# HybrideNixieClock.net
KiCad netlist of a schematic drawn in EAGLE
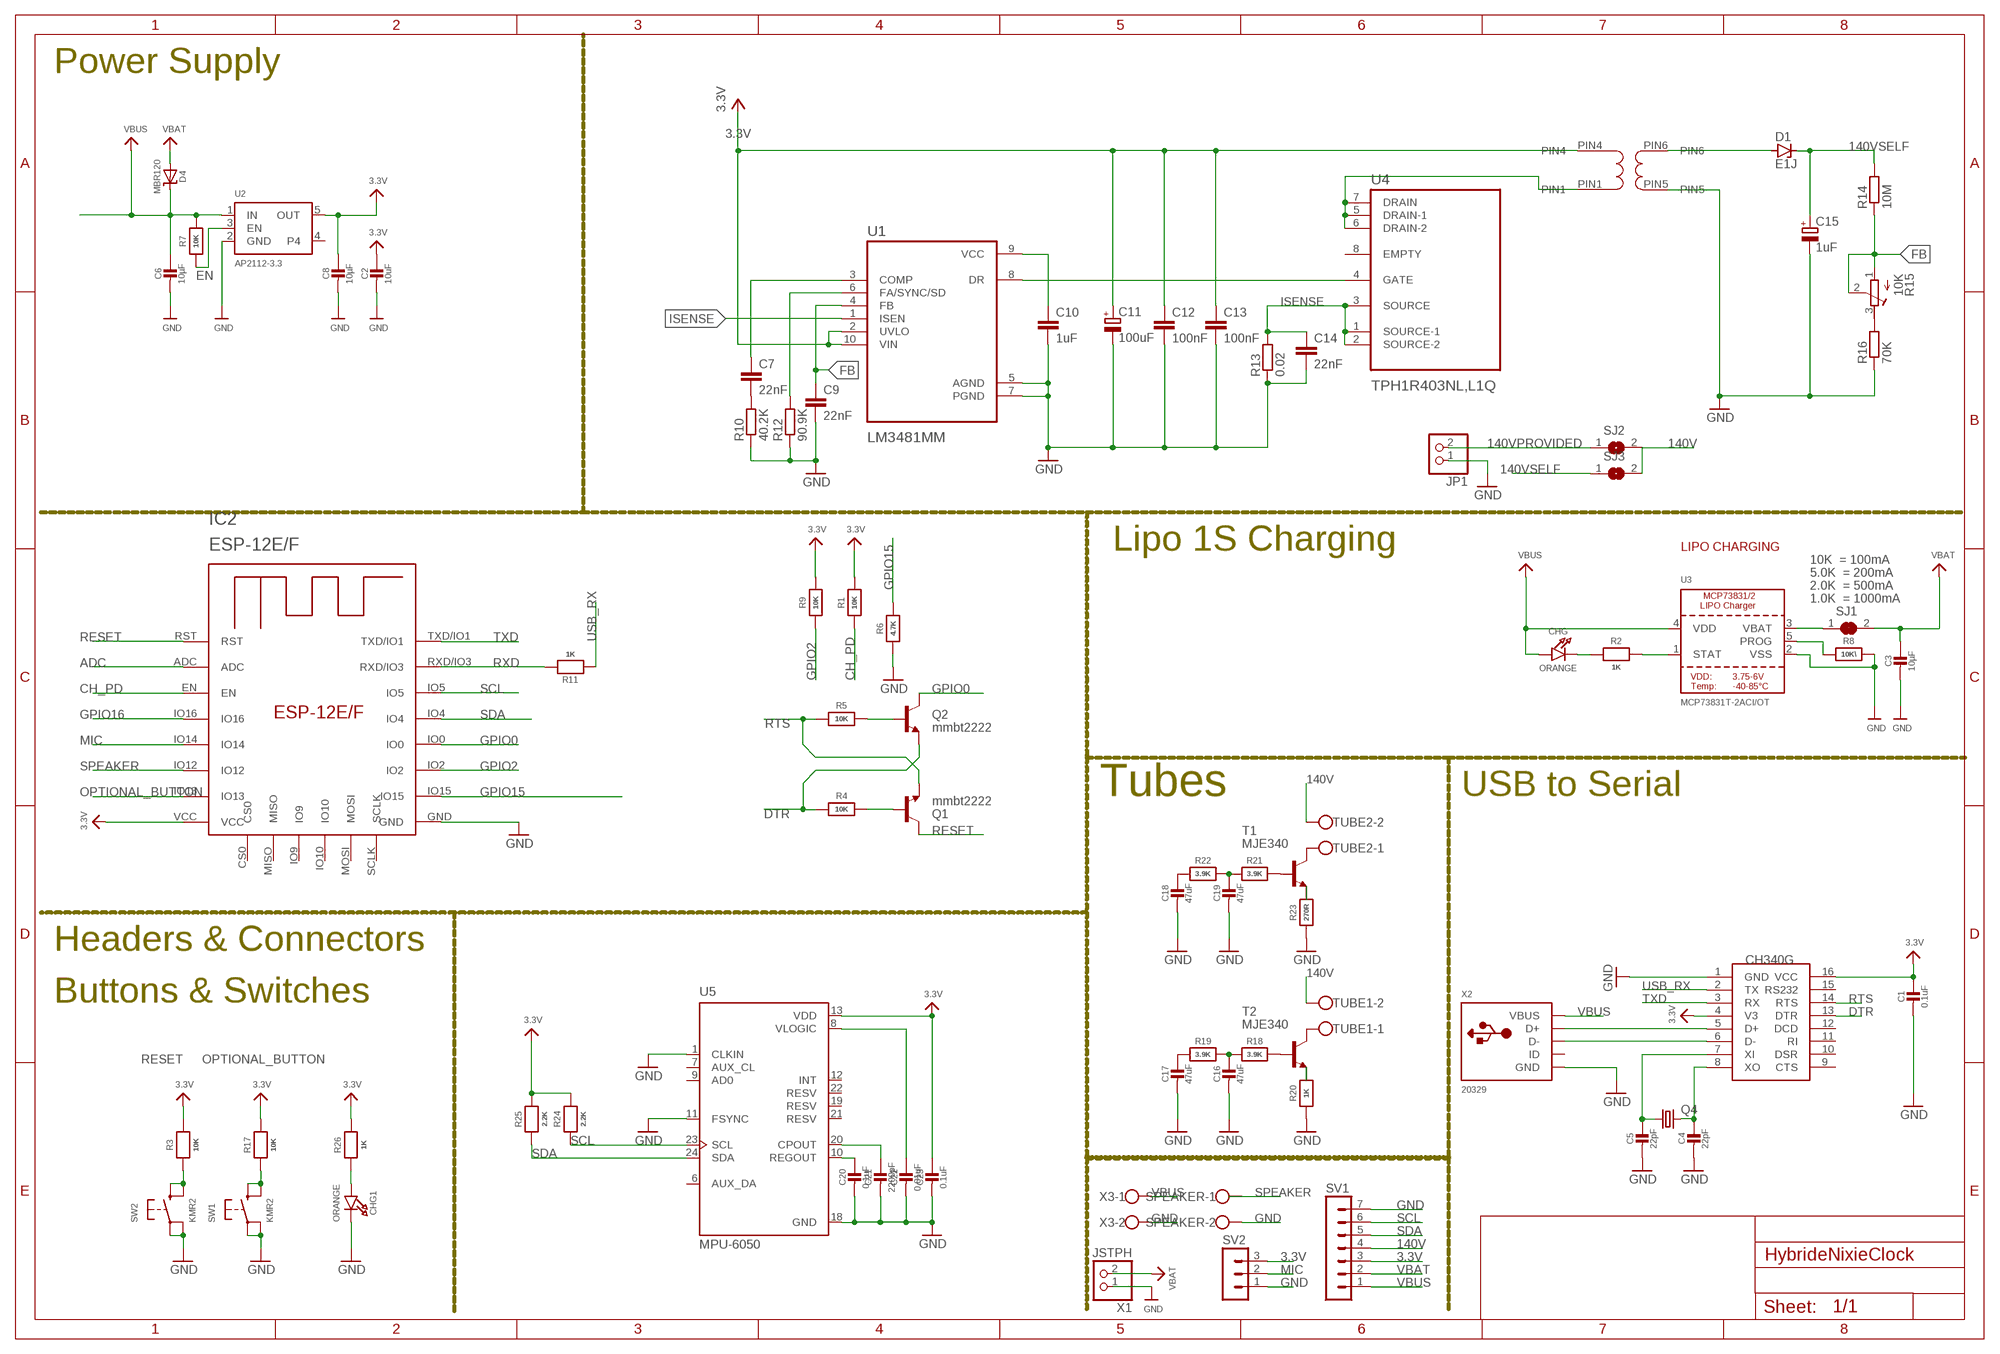
[diagram p0: schematic, sheet 1]

(export (version "E")
  (design (tool "Eeschema 10.0.6"))
  (components
    (comp (ref "C1")
      (value "0.1uF")
      (footprint "eagle-import:0603-NO")
      (libsource (lib "eagle-import") (part "CAP_CERAMIC0603_NO"))
    )
    (comp (ref "C2")
      (value "10uF")
      (footprint "eagle-import:0805-NO")
      (libsource (lib "eagle-import") (part "CAP_CERAMIC0805-NOOUTLINE"))
    )
    (comp (ref "C3")
      (value "10µF")
      (footprint "eagle-import:0805-NO")
      (libsource (lib "eagle-import") (part "CAP_CERAMIC0805-NOOUTLINE"))
    )
    (comp (ref "C4")
      (value "22pF")
      (footprint "eagle-import:0603-NO")
      (libsource (lib "eagle-import") (part "CAP_CERAMIC0603_NO"))
    )
    (comp (ref "C5")
      (value "22pF")
      (footprint "eagle-import:0603-NO")
      (libsource (lib "eagle-import") (part "CAP_CERAMIC0603_NO"))
    )
    (comp (ref "C6")
      (value "10µF")
      (footprint "eagle-import:0805-NO")
      (libsource (lib "eagle-import") (part "CAP_CERAMIC0805-NOOUTLINE"))
    )
    (comp (ref "C7")
      (value "22nF")
      (footprint "eagle-import:C0603")
      (libsource (lib "eagle-import") (part "C-EUC0603"))
    )
    (comp (ref "C8")
      (value "10µF")
      (footprint "eagle-import:0805-NO")
      (libsource (lib "eagle-import") (part "CAP_CERAMIC0805-NOOUTLINE"))
    )
    (comp (ref "C9")
      (value "22nF")
      (footprint "eagle-import:C0603")
      (libsource (lib "eagle-import") (part "C-EUC0603"))
    )
    (comp (ref "C10")
      (value "1uF")
      (footprint "eagle-import:C0603")
      (libsource (lib "eagle-import") (part "C-EUC0603"))
    )
    (comp (ref "C11")
      (value "100uF")
      (footprint "eagle-import:CT3216")
      (libsource (lib "eagle-import") (part "CPOL-EUCT3216"))
    )
    (comp (ref "C12")
      (value "100nF")
      (footprint "eagle-import:C0603")
      (libsource (lib "eagle-import") (part "C-EUC0603"))
    )
    (comp (ref "C13")
      (value "100nF")
      (footprint "eagle-import:C0603")
      (libsource (lib "eagle-import") (part "C-EUC0603"))
    )
    (comp (ref "C14")
      (value "22nF")
      (footprint "eagle-import:C0603")
      (libsource (lib "eagle-import") (part "C-EUC0603"))
    )
    (comp (ref "C15")
      (value "1uF")
      (footprint "eagle-import:CT3216")
      (libsource (lib "eagle-import") (part "CPOL-EUCT3216"))
    )
    (comp (ref "C16")
      (value "47uF")
      (footprint "eagle-import:0603-NO")
      (libsource (lib "eagle-import") (part "CAP_CERAMIC0603_NO"))
    )
    (comp (ref "C17")
      (value "47uF")
      (footprint "eagle-import:0603-NO")
      (libsource (lib "eagle-import") (part "CAP_CERAMIC0603_NO"))
    )
    (comp (ref "C18")
      (value "47uF")
      (footprint "eagle-import:0603-NO")
      (libsource (lib "eagle-import") (part "CAP_CERAMIC0603_NO"))
    )
    (comp (ref "C19")
      (value "47uF")
      (footprint "eagle-import:0603-NO")
      (libsource (lib "eagle-import") (part "CAP_CERAMIC0603_NO"))
    )
    (comp (ref "C20")
      (value "0.1uF")
      (footprint "eagle-import:0603-NO")
      (libsource (lib "eagle-import") (part "CAP_CERAMIC0603_NO"))
    )
    (comp (ref "C21")
      (value "2200pF")
      (footprint "eagle-import:0603-NO")
      (libsource (lib "eagle-import") (part "CAP_CERAMIC0603_NO"))
    )
    (comp (ref "C22")
      (value "0.01uF")
      (footprint "eagle-import:0603-NO")
      (libsource (lib "eagle-import") (part "CAP_CERAMIC0603_NO"))
    )
    (comp (ref "C23")
      (value "0.1uF")
      (footprint "eagle-import:0603-NO")
      (libsource (lib "eagle-import") (part "CAP_CERAMIC0603_NO"))
    )
    (comp (ref "CHG")
      (value "ORANGE")
      (footprint "eagle-import:CHIPLED_0805_NOOUTLINE")
      (libsource (lib "eagle-import") (part "LED0805_NOOUTLINE"))
    )
    (comp (ref "CHG1")
      (value "ORANGE")
      (footprint "eagle-import:CHIPLED_0805_NOOUTLINE")
      (libsource (lib "eagle-import") (part "LED0805_NOOUTLINE"))
    )
    (comp (ref "D1")
      (value "E1J")
      (footprint "eagle-import:SMB")
      (libsource (lib "eagle-import") (part "ZENER-DIODESMB"))
    )
    (comp (ref "D4")
      (value "MBR120")
      (footprint "eagle-import:SOD-123")
      (libsource (lib "eagle-import") (part "DIODE-SCHOTTKYSOD-123"))
    )
    (comp (ref "IC2")
      (value "ESP-12E/F")
      (footprint "eagle-import:ESP-12E")
      (libsource (lib "eagle-import") (part "ESP-12E/F"))
    )
    (comp (ref "JP1")
      (value "PINHD-1X2")
      (footprint "eagle-import:1X02")
      (libsource (lib "eagle-import") (part "PINHD-1X2"))
    )
    (comp (ref "Q1")
      (value "mmbt2222")
      (footprint "eagle-import:SOT23-3")
      (libsource (lib "eagle-import") (part "TRANSISTOR_NPNSOT23-3"))
    )
    (comp (ref "Q2")
      (value "mmbt2222")
      (footprint "eagle-import:SOT23-3")
      (libsource (lib "eagle-import") (part "TRANSISTOR_NPNSOT23-3"))
    )
    (comp (ref "Q4")
      (value "CRYSTALCTS406")
      (footprint "eagle-import:CTS406")
      (libsource (lib "eagle-import") (part "CRYSTALCTS406"))
    )
    (comp (ref "R1")
      (value "10K")
      (footprint "eagle-import:0603-NO")
      (libsource (lib "eagle-import") (part "RESISTOR_0603_NOOUT"))
    )
    (comp (ref "R2")
      (value "1K")
      (footprint "eagle-import:0603-NO")
      (libsource (lib "eagle-import") (part "RESISTOR_0603_NOOUT"))
    )
    (comp (ref "R3")
      (value "10K")
      (footprint "eagle-import:0603-NO")
      (libsource (lib "eagle-import") (part "RESISTOR_0603_NOOUT"))
    )
    (comp (ref "R4")
      (value "10K")
      (footprint "eagle-import:0603-NO")
      (libsource (lib "eagle-import") (part "RESISTOR_0603_NOOUT"))
    )
    (comp (ref "R5")
      (value "10K")
      (footprint "eagle-import:0603-NO")
      (libsource (lib "eagle-import") (part "RESISTOR_0603_NOOUT"))
    )
    (comp (ref "R6")
      (value "4.7K")
      (footprint "eagle-import:0603-NO")
      (libsource (lib "eagle-import") (part "RESISTOR_0603_NOOUT"))
    )
    (comp (ref "R7")
      (value "10K")
      (footprint "eagle-import:0603-NO")
      (libsource (lib "eagle-import") (part "RESISTOR_0603_NOOUT"))
    )
    (comp (ref "R8")
      (value "10K\\")
      (footprint "eagle-import:0603-NO")
      (libsource (lib "eagle-import") (part "RESISTOR_0603_NOOUT"))
    )
    (comp (ref "R9")
      (value "10K")
      (footprint "eagle-import:0603-NO")
      (libsource (lib "eagle-import") (part "RESISTOR_0603_NOOUT"))
    )
    (comp (ref "R10")
      (value "40.2K")
      (footprint "eagle-import:R0603")
      (libsource (lib "eagle-import") (part "R-EU_R0603"))
    )
    (comp (ref "R11")
      (value "1K")
      (footprint "eagle-import:_0603MP")
      (libsource (lib "eagle-import") (part "RESISTOR_0603MP"))
    )
    (comp (ref "R12")
      (value "90.9K")
      (footprint "eagle-import:R0603")
      (libsource (lib "eagle-import") (part "R-EU_R0603"))
    )
    (comp (ref "R13")
      (value "0.02")
      (footprint "eagle-import:R0603")
      (libsource (lib "eagle-import") (part "R-EU_R0603"))
    )
    (comp (ref "R14")
      (value "10M")
      (footprint "eagle-import:R0603")
      (libsource (lib "eagle-import") (part "R-EU_R0603"))
    )
    (comp (ref "R15")
      (value "10K")
      (footprint "eagle-import:RTRIM4G_J")
      (libsource (lib "eagle-import") (part "R-TRIMM4G/J"))
    )
    (comp (ref "R16")
      (value "70K")
      (footprint "eagle-import:R0603")
      (libsource (lib "eagle-import") (part "R-EU_R0603"))
    )
    (comp (ref "R17")
      (value "10K")
      (footprint "eagle-import:0603-NO")
      (libsource (lib "eagle-import") (part "RESISTOR_0603_NOOUT"))
    )
    (comp (ref "R18")
      (value "3.9K")
      (footprint "eagle-import:0603-NO")
      (libsource (lib "eagle-import") (part "RESISTOR_0603_NOOUT"))
    )
    (comp (ref "R19")
      (value "3.9K")
      (footprint "eagle-import:0603-NO")
      (libsource (lib "eagle-import") (part "RESISTOR_0603_NOOUT"))
    )
    (comp (ref "R20")
      (value "1K")
      (footprint "eagle-import:0603-NO")
      (libsource (lib "eagle-import") (part "RESISTOR_0603_NOOUT"))
    )
    (comp (ref "R21")
      (value "3.9K")
      (footprint "eagle-import:0603-NO")
      (libsource (lib "eagle-import") (part "RESISTOR_0603_NOOUT"))
    )
    (comp (ref "R22")
      (value "3.9K")
      (footprint "eagle-import:0603-NO")
      (libsource (lib "eagle-import") (part "RESISTOR_0603_NOOUT"))
    )
    (comp (ref "R23")
      (value "270R")
      (footprint "eagle-import:0603-NO")
      (libsource (lib "eagle-import") (part "RESISTOR_0603_NOOUT"))
    )
    (comp (ref "R24")
      (value "2.2K")
      (footprint "eagle-import:0603-NO")
      (libsource (lib "eagle-import") (part "RESISTOR_0603_NOOUT"))
    )
    (comp (ref "R25")
      (value "2.2K")
      (footprint "eagle-import:0603-NO")
      (libsource (lib "eagle-import") (part "RESISTOR_0603_NOOUT"))
    )
    (comp (ref "R26")
      (value "1K")
      (footprint "eagle-import:0603-NO")
      (libsource (lib "eagle-import") (part "RESISTOR_0603_NOOUT"))
    )
    (comp (ref "SJ1")
      (value "SOLDERJUMPER_CLOSED")
      (footprint "eagle-import:SOLDERJUMPER_CLOSEDWIRE")
      (libsource (lib "eagle-import") (part "SOLDERJUMPER_CLOSED"))
    )
    (comp (ref "SJ2") (value "SJ") (footprint "eagle-import:SJ") (libsource (lib "eagle-import") (part "SJ")))
    (comp (ref "SJ3") (value "SJ") (footprint "eagle-import:SJ") (libsource (lib "eagle-import") (part "SJ")))
    (comp (ref "SPEAKER")
      (value "W237-102")
      (footprint "eagle-import:W237-102")
      (fields (field (name "MPN") "237-102"))
      (libsource (lib "eagle-import") (part "W237-102"))
    )
    (comp (ref "SV1")
      (value "MA07-1")
      (footprint "eagle-import:MA07-1")
      (libsource (lib "eagle-import") (part "MA07-1"))
    )
    (comp (ref "SV2")
      (value "MA03-1")
      (footprint "eagle-import:MA03-1")
      (libsource (lib "eagle-import") (part "MA03-1"))
    )
    (comp (ref "SW1")
      (value "KMR2")
      (footprint "eagle-import:BTN_KMR2_4.6X2.8")
      (libsource (lib "eagle-import") (part "SWITCH_TACT_SMT4.6X2.8"))
    )
    (comp (ref "SW2")
      (value "KMR2")
      (footprint "eagle-import:BTN_KMR2_4.6X2.8")
      (libsource (lib "eagle-import") (part "SWITCH_TACT_SMT4.6X2.8"))
    )
    (comp (ref "T1")
      (value "MJE340")
      (footprint "eagle-import:TO126")
      (fields (field (name "MF") "STMicroelectronics"))
      (libsource (lib "eagle-import") (part "MJE340"))
    )
    (comp (ref "T2")
      (value "MJE340")
      (footprint "eagle-import:TO126")
      (fields (field (name "MF") "STMicroelectronics"))
      (libsource (lib "eagle-import") (part "MJE340"))
    )
    (comp (ref "TUBE1")
      (value "W237-102")
      (footprint "eagle-import:W237-102")
      (fields (field (name "MPN") "237-102"))
      (libsource (lib "eagle-import") (part "W237-102"))
    )
    (comp (ref "TUBE2")
      (value "W237-102")
      (footprint "eagle-import:W237-102")
      (fields (field (name "MPN") "237-102"))
      (libsource (lib "eagle-import") (part "W237-102"))
    )
    (comp (ref "U$6")
      (value "TTRN-060S-013")
      (footprint "eagle-import:TTRN-060S-013")
      (libsource (lib "eagle-import") (part "TTRN-060S-013"))
    )
    (comp (ref "U$7")
      (value "CH340G")
      (footprint "eagle-import:SOIC16")
      (libsource (lib "eagle-import") (part "CH340G"))
    )
    (comp (ref "U1")
      (value "LM3481MM")
      (footprint "eagle-import:SOP50P490X110-10N")
      (fields (field (name "MF") "Texas Instruments") (field (name "MP") "LM3481MM/NOPB"))
      (libsource (lib "eagle-import") (part "LM3481MM"))
    )
    (comp (ref "U2")
      (value "AP2112-3.3")
      (footprint "eagle-import:SOT23-5")
      (libsource (lib "eagle-import") (part "VREG_SOT23-5"))
    )
    (comp (ref "U3")
      (value "MCP73831T-2ACI/OT")
      (footprint "eagle-import:SOT23-5")
      (libsource (lib "eagle-import") (part "MCP73831/2"))
    )
    (comp (ref "U4")
      (value "TPH1R403NL,L1Q")
      (footprint "eagle-import:TRANS_TPHR8504PL,L1Q")
      (fields (field (name "MF") "Toshiba Semiconductor"))
      (libsource (lib "eagle-import") (part "TPH1R403NL,L1Q"))
    )
    (comp (ref "U5")
      (value "MPU-6050")
      (footprint "eagle-import:QFN50P400X400X95-24N")
      (fields (field (name "MF") "TDK InvenSense"))
      (libsource (lib "eagle-import") (part "MPU-6050"))
    )
    (comp (ref "X1")
      (value "JSTPH")
      (footprint "eagle-import:JSTPH2")
      (libsource (lib "eagle-import") (part "CON_JST_PH_2PIN"))
    )
    (comp (ref "X2")
      (value "20329")
      (footprint "eagle-import:4UCONN_20329_V2")
      (libsource (lib "eagle-import") (part "USB_MICRO_20329_V2"))
    )
    (comp (ref "X3")
      (value "W237-102")
      (footprint "eagle-import:W237-102")
      (fields (field (name "MPN") "237-102"))
      (libsource (lib "eagle-import") (part "W237-102"))
    )
  )
  (nets
    (net (code "1") (name "/140V") (class "Default")
      (node (ref "SJ2") (pin "2") (pinfunction "2_2") (pintype "passive"))
      (node (ref "SJ3") (pin "2") (pinfunction "2_2") (pintype "passive"))
      (node (ref "SV1") (pin "4") (pinfunction "4_4") (pintype "passive"))
      (node (ref "TUBE1") (pin "2") (pinfunction "KL_2") (pintype "passive"))
      (node (ref "TUBE2") (pin "2") (pinfunction "KL_2") (pintype "passive"))
    )
    (net (code "2") (name "/140VPROVIDED") (class "Default")
      (node (ref "JP1") (pin "2") (pinfunction "2_2") (pintype "passive"))
      (node (ref "SJ2") (pin "1") (pinfunction "1_1") (pintype "passive"))
    )
    (net (code "3") (name "/140VSELF") (class "Default")
      (node (ref "C15") (pin "+") (pinfunction "+_+") (pintype "passive"))
      (node (ref "D1") (pin "C") (pinfunction "C_C") (pintype "passive"))
      (node (ref "R14") (pin "2") (pinfunction "2_2") (pintype "passive"))
      (node (ref "SJ3") (pin "1") (pinfunction "1_1") (pintype "passive"))
    )
    (net (code "4") (name "/ADC") (class "Default")
      (node (ref "IC2") (pin "ADC") (pinfunction "ADC_ADC") (pintype "bidirectional"))
    )
    (net (code "5") (name "/CH_PD") (class "Default")
      (node (ref "IC2") (pin "EN") (pinfunction "EN_EN") (pintype "bidirectional"))
      (node (ref "R1") (pin "1") (pinfunction "1_1") (pintype "passive"))
    )
    (net (code "6") (name "/DTR") (class "Default")
      (node (ref "Q2") (pin "2") (pinfunction "E_2") (pintype "passive"))
      (node (ref "R4") (pin "1") (pinfunction "1_1") (pintype "passive"))
      (node (ref "U$7") (pin "13") (pinfunction "DTR_13") (pintype "bidirectional"))
    )
    (net (code "7") (name "/EN") (class "Default")
      (node (ref "R7") (pin "1") (pinfunction "1_1") (pintype "passive"))
      (node (ref "U2") (pin "3") (pinfunction "EN_3") (pintype "input"))
    )
    (net (code "8") (name "/GPIO0") (class "Default")
      (node (ref "IC2") (pin "IO0") (pinfunction "IO0_IO0") (pintype "bidirectional"))
      (node (ref "Q2") (pin "3") (pinfunction "C_3") (pintype "passive"))
    )
    (net (code "9") (name "/GPIO2") (class "Default")
      (node (ref "IC2") (pin "IO2") (pinfunction "IO2_IO2") (pintype "bidirectional"))
      (node (ref "R9") (pin "1") (pinfunction "1_1") (pintype "passive"))
    )
    (net (code "10") (name "/GPIO15") (class "Default")
      (node (ref "IC2") (pin "IO15") (pinfunction "IO15_IO15") (pintype "bidirectional"))
      (node (ref "R6") (pin "2") (pinfunction "2_2") (pintype "passive"))
    )
    (net (code "11") (name "/GPIO16") (class "Default")
      (node (ref "IC2") (pin "IO16") (pinfunction "IO16_IO16") (pintype "bidirectional"))
    )
    (net (code "12") (name "/MIC") (class "Default")
      (node (ref "IC2") (pin "IO14") (pinfunction "IO14_IO14") (pintype "bidirectional"))
      (node (ref "SV2") (pin "2") (pinfunction "2_2") (pintype "passive"))
    )
    (net (code "13") (name "/N$11") (class "Default")
      (node (ref "D1") (pin "A") (pinfunction "A_A") (pintype "passive"))
      (node (ref "U$6") (pin "PIN6") (pinfunction "PIN6_PIN6") (pintype "bidirectional"))
      (node (ref "U1") (pin "8") (pinfunction "DR_8") (pintype "output"))
      (node (ref "U4") (pin "4") (pinfunction "GATE_4") (pintype "bidirectional"))
    )
    (net (code "14") (name "/OPTIONAL_BUTTON") (class "Default")
      (node (ref "IC2") (pin "IO13") (pinfunction "IO13_IO13") (pintype "bidirectional"))
      (node (ref "R17") (pin "1") (pinfunction "1_1") (pintype "passive"))
      (node (ref "SW1") (pin "B") (pinfunction "S_B") (pintype "passive"))
      (node (ref "SW1") (pin "B'") (pinfunction "S1_B'") (pintype "passive"))
    )
    (net (code "15") (name "/RESET") (class "Default")
      (node (ref "IC2") (pin "RST") (pinfunction "RST_RST") (pintype "input"))
      (node (ref "Q1") (pin "3") (pinfunction "C_3") (pintype "passive"))
      (node (ref "R3") (pin "1") (pinfunction "1_1") (pintype "passive"))
      (node (ref "SW2") (pin "B") (pinfunction "S_B") (pintype "passive"))
      (node (ref "SW2") (pin "B'") (pinfunction "S1_B'") (pintype "passive"))
    )
    (net (code "16") (name "/RTS") (class "Default")
      (node (ref "Q1") (pin "2") (pinfunction "E_2") (pintype "passive"))
      (node (ref "R5") (pin "1") (pinfunction "1_1") (pintype "passive"))
      (node (ref "U$7") (pin "14") (pinfunction "RTS_14") (pintype "bidirectional"))
    )
    (net (code "17") (name "/RXD") (class "Default")
      (node (ref "IC2") (pin "RXD/IO3") (pinfunction "RXD/IO3_RXD/IO3") (pintype "bidirectional"))
      (node (ref "R11") (pin "2") (pinfunction "2_2") (pintype "passive"))
    )
    (net (code "18") (name "/SCL") (class "Default")
      (node (ref "IC2") (pin "IO5") (pinfunction "IO5_IO5") (pintype "bidirectional"))
      (node (ref "R24") (pin "1") (pinfunction "1_1") (pintype "passive"))
      (node (ref "SV1") (pin "6") (pinfunction "6_6") (pintype "passive"))
      (node (ref "U5") (pin "23") (pinfunction "SCL_23") (pintype "input"))
    )
    (net (code "19") (name "/SDA") (class "Default")
      (node (ref "IC2") (pin "IO4") (pinfunction "IO4_IO4") (pintype "bidirectional"))
      (node (ref "R25") (pin "1") (pinfunction "1_1") (pintype "passive"))
      (node (ref "SV1") (pin "5") (pinfunction "5_5") (pintype "passive"))
      (node (ref "U5") (pin "24") (pinfunction "SDA_24") (pintype "bidirectional"))
    )
    (net (code "20") (name "/SPEAKER") (class "Default")
      (node (ref "IC2") (pin "IO12") (pinfunction "IO12_IO12") (pintype "bidirectional"))
      (node (ref "SPEAKER") (pin "1") (pinfunction "KL_1") (pintype "passive"))
    )
    (net (code "21") (name "/TXD") (class "Default")
      (node (ref "IC2") (pin "TXD/IO1") (pinfunction "TXD/IO1_TXD/IO1") (pintype "bidirectional"))
      (node (ref "U$7") (pin "3") (pinfunction "RX_3") (pintype "bidirectional"))
    )
    (net (code "22") (name "/USB_RX") (class "Default")
      (node (ref "R11") (pin "1") (pinfunction "1_1") (pintype "passive"))
      (node (ref "U$7") (pin "2") (pinfunction "TX_2") (pintype "bidirectional"))
    )
    (net (code "23") (name "3.3V") (class "Default")
      (node (ref "C1") (pin "1") (pinfunction "1_1") (pintype "passive"))
      (node (ref "C11") (pin "+") (pinfunction "+_+") (pintype "passive"))
      (node (ref "C12") (pin "1") (pinfunction "1_1") (pintype "passive"))
      (node (ref "C13") (pin "1") (pinfunction "1_1") (pintype "passive"))
      (node (ref "C2") (pin "1") (pinfunction "1_1") (pintype "passive"))
      (node (ref "C23") (pin "1") (pinfunction "1_1") (pintype "passive"))
      (node (ref "C8") (pin "1") (pinfunction "1_1") (pintype "passive"))
      (node (ref "IC2") (pin "VCC") (pinfunction "VCC_VCC") (pintype "power_in"))
      (node (ref "R1") (pin "2") (pinfunction "2_2") (pintype "passive"))
      (node (ref "R17") (pin "2") (pinfunction "2_2") (pintype "passive"))
      (node (ref "R24") (pin "2") (pinfunction "2_2") (pintype "passive"))
      (node (ref "R25") (pin "2") (pinfunction "2_2") (pintype "passive"))
      (node (ref "R26") (pin "2") (pinfunction "2_2") (pintype "passive"))
      (node (ref "R3") (pin "2") (pinfunction "2_2") (pintype "passive"))
      (node (ref "R9") (pin "2") (pinfunction "2_2") (pintype "passive"))
      (node (ref "SV1") (pin "3") (pinfunction "3_3") (pintype "passive"))
      (node (ref "SV2") (pin "3") (pinfunction "3_3") (pintype "passive"))
      (node (ref "U$6") (pin "PIN4") (pinfunction "PIN4_PIN4") (pintype "bidirectional"))
      (node (ref "U$7") (pin "16") (pinfunction "VCC_16") (pintype "bidirectional"))
      (node (ref "U$7") (pin "4") (pinfunction "V3_4") (pintype "bidirectional"))
      (node (ref "U1") (pin "10") (pinfunction "VIN_10") (pintype "input"))
      (node (ref "U1") (pin "2") (pinfunction "UVLO_2") (pintype "input"))
      (node (ref "U2") (pin "5") (pinfunction "OUT_5") (pintype "power_in"))
      (node (ref "U5") (pin "13") (pinfunction "VDD_13") (pintype "power_in"))
    )
    (net (code "24") (name "FB") (class "Default")
      (node (ref "C9") (pin "1") (pinfunction "1_1") (pintype "passive"))
      (node (ref "R14") (pin "1") (pinfunction "1_1") (pintype "passive"))
      (node (ref "R15") (pin "1") (pinfunction "A_1") (pintype "passive"))
      (node (ref "R15") (pin "2") (pinfunction "S_2") (pintype "passive"))
      (node (ref "U1") (pin "4") (pinfunction "FB_4") (pintype "input"))
    )
    (net (code "25") (name "GND") (class "Default")
      (node (ref "C1") (pin "2") (pinfunction "2_2") (pintype "passive"))
      (node (ref "C10") (pin "2") (pinfunction "2_2") (pintype "passive"))
      (node (ref "C11") (pin "-") (pinfunction "-_-") (pintype "passive"))
      (node (ref "C12") (pin "2") (pinfunction "2_2") (pintype "passive"))
      (node (ref "C13") (pin "2") (pinfunction "2_2") (pintype "passive"))
      (node (ref "C14") (pin "2") (pinfunction "2_2") (pintype "passive"))
      (node (ref "C15") (pin "-") (pinfunction "-_-") (pintype "passive"))
      (node (ref "C16") (pin "2") (pinfunction "2_2") (pintype "passive"))
      (node (ref "C17") (pin "2") (pinfunction "2_2") (pintype "passive"))
      (node (ref "C18") (pin "2") (pinfunction "2_2") (pintype "passive"))
      (node (ref "C19") (pin "2") (pinfunction "2_2") (pintype "passive"))
      (node (ref "C2") (pin "2") (pinfunction "2_2") (pintype "passive"))
      (node (ref "C20") (pin "2") (pinfunction "2_2") (pintype "passive"))
      (node (ref "C21") (pin "2") (pinfunction "2_2") (pintype "passive"))
      (node (ref "C22") (pin "2") (pinfunction "2_2") (pintype "passive"))
      (node (ref "C23") (pin "2") (pinfunction "2_2") (pintype "passive"))
      (node (ref "C3") (pin "2") (pinfunction "2_2") (pintype "passive"))
      (node (ref "C4") (pin "2") (pinfunction "2_2") (pintype "passive"))
      (node (ref "C5") (pin "2") (pinfunction "2_2") (pintype "passive"))
      (node (ref "C6") (pin "2") (pinfunction "2_2") (pintype "passive"))
      (node (ref "C8") (pin "2") (pinfunction "2_2") (pintype "passive"))
      (node (ref "C9") (pin "2") (pinfunction "2_2") (pintype "passive"))
      (node (ref "CHG1") (pin "C") (pinfunction "C_C") (pintype "passive"))
      (node (ref "IC2") (pin "GND") (pinfunction "GND_GND") (pintype "power_in"))
      (node (ref "JP1") (pin "1") (pinfunction "1_1") (pintype "passive"))
      (node (ref "R10") (pin "1") (pinfunction "1_1") (pintype "passive"))
      (node (ref "R12") (pin "1") (pinfunction "1_1") (pintype "passive"))
      (node (ref "R13") (pin "1") (pinfunction "1_1") (pintype "passive"))
      (node (ref "R16") (pin "1") (pinfunction "1_1") (pintype "passive"))
      (node (ref "R20") (pin "1") (pinfunction "1_1") (pintype "passive"))
      (node (ref "R23") (pin "1") (pinfunction "1_1") (pintype "passive"))
      (node (ref "R6") (pin "1") (pinfunction "1_1") (pintype "passive"))
      (node (ref "R8") (pin "2") (pinfunction "2_2") (pintype "passive"))
      (node (ref "SPEAKER") (pin "2") (pinfunction "KL_2") (pintype "passive"))
      (node (ref "SV1") (pin "7") (pinfunction "7_7") (pintype "passive"))
      (node (ref "SV2") (pin "1") (pinfunction "1_1") (pintype "passive"))
      (node (ref "SW1") (pin "A") (pinfunction "P_A") (pintype "passive"))
      (node (ref "SW1") (pin "A'") (pinfunction "P1_A'") (pintype "passive"))
      (node (ref "SW2") (pin "A") (pinfunction "P_A") (pintype "passive"))
      (node (ref "SW2") (pin "A'") (pinfunction "P1_A'") (pintype "passive"))
      (node (ref "U$6") (pin "PIN5") (pinfunction "PIN5_PIN5") (pintype "bidirectional"))
      (node (ref "U$7") (pin "1") (pinfunction "GND_1") (pintype "bidirectional"))
      (node (ref "U1") (pin "5") (pinfunction "AGND_5") (pintype "power_in"))
      (node (ref "U1") (pin "7") (pinfunction "PGND_7") (pintype "power_in"))
      (node (ref "U2") (pin "2") (pinfunction "GND_2") (pintype "power_in"))
      (node (ref "U3") (pin "2") (pinfunction "VSS_2") (pintype "power_in"))
      (node (ref "U5") (pin "1") (pinfunction "CLKIN_1") (pintype "input"))
      (node (ref "U5") (pin "11") (pinfunction "FSYNC_11") (pintype "input"))
      (node (ref "U5") (pin "18") (pinfunction "GND_18") (pintype "power_in"))
      (node (ref "X1") (pin "1") (pinfunction "1_1") (pintype "passive"))
      (node (ref "X2") (pin "BASE@1") (pinfunction "GND_BASE@1") (pintype "power_in"))
      (node (ref "X2") (pin "BASE@2") (pinfunction "GND_BASE@2") (pintype "power_in"))
      (node (ref "X2") (pin "GND") (pinfunction "GND_GND") (pintype "power_in"))
      (node (ref "X2") (pin "SPRT@1") (pinfunction "GND_SPRT@1") (pintype "power_in"))
      (node (ref "X2") (pin "SPRT@2") (pinfunction "GND_SPRT@2") (pintype "power_in"))
      (node (ref "X2") (pin "SPRT@3") (pinfunction "GND_SPRT@3") (pintype "power_in"))
      (node (ref "X2") (pin "SPRT@4") (pinfunction "GND_SPRT@4") (pintype "power_in"))
      (node (ref "X3") (pin "2") (pinfunction "KL_2") (pintype "passive"))
    )
    (net (code "26") (name "ISENSE") (class "Default")
      (node (ref "C14") (pin "1") (pinfunction "1_1") (pintype "passive"))
      (node (ref "R13") (pin "2") (pinfunction "2_2") (pintype "passive"))
      (node (ref "U1") (pin "1") (pinfunction "ISEN_1") (pintype "input"))
      (node (ref "U4") (pin "1") (pinfunction "SOURCE-1_1") (pintype "bidirectional"))
      (node (ref "U4") (pin "2") (pinfunction "SOURCE-2_2") (pintype "bidirectional"))
      (node (ref "U4") (pin "3") (pinfunction "SOURCE_3") (pintype "bidirectional"))
    )
    (net (code "27") (name "Net-(C7-Pad2)") (class "Default")
      (node (ref "C7") (pin "2") (pinfunction "2_2") (pintype "passive"))
      (node (ref "R10") (pin "2") (pinfunction "2_2") (pintype "passive"))
    )
    (net (code "28") (name "Net-(C16-Pad1)") (class "Default")
      (node (ref "C16") (pin "1") (pinfunction "1_1") (pintype "passive"))
      (node (ref "R18") (pin "1") (pinfunction "1_1") (pintype "passive"))
      (node (ref "R19") (pin "2") (pinfunction "2_2") (pintype "passive"))
    )
    (net (code "29") (name "Net-(C17-Pad1)") (class "Default")
      (node (ref "C17") (pin "1") (pinfunction "1_1") (pintype "passive"))
      (node (ref "R19") (pin "1") (pinfunction "1_1") (pintype "passive"))
    )
    (net (code "30") (name "Net-(C18-Pad1)") (class "Default")
      (node (ref "C18") (pin "1") (pinfunction "1_1") (pintype "passive"))
      (node (ref "R22") (pin "1") (pinfunction "1_1") (pintype "passive"))
    )
    (net (code "31") (name "Net-(C19-Pad1)") (class "Default")
      (node (ref "C19") (pin "1") (pinfunction "1_1") (pintype "passive"))
      (node (ref "R21") (pin "1") (pinfunction "1_1") (pintype "passive"))
      (node (ref "R22") (pin "2") (pinfunction "2_2") (pintype "passive"))
    )
    (net (code "32") (name "Net-(CHG-PadC)") (class "Default")
      (node (ref "CHG") (pin "C") (pinfunction "C_C") (pintype "passive"))
      (node (ref "R2") (pin "1") (pinfunction "1_1") (pintype "passive"))
    )
    (net (code "33") (name "Net-(CHG1-PadA)") (class "Default")
      (node (ref "CHG1") (pin "A") (pinfunction "A_A") (pintype "passive"))
      (node (ref "R26") (pin "1") (pinfunction "1_1") (pintype "passive"))
    )
    (net (code "34") (name "Net-(Q1-B)") (class "Default")
      (node (ref "Q1") (pin "1") (pinfunction "B_1") (pintype "passive"))
      (node (ref "R4") (pin "2") (pinfunction "2_2") (pintype "passive"))
    )
    (net (code "35") (name "Net-(Q2-B)") (class "Default")
      (node (ref "Q2") (pin "1") (pinfunction "B_1") (pintype "passive"))
      (node (ref "R5") (pin "2") (pinfunction "2_2") (pintype "passive"))
    )
    (net (code "36") (name "Net-(Q4-2)") (class "Default")
      (node (ref "C4") (pin "1") (pinfunction "1_1") (pintype "passive"))
      (node (ref "Q4") (pin "3") (pinfunction "2_3") (pintype "passive"))
      (node (ref "U$7") (pin "8") (pinfunction "XO_8") (pintype "bidirectional"))
    )
    (net (code "37") (name "Net-(R15-E)") (class "Default")
      (node (ref "R15") (pin "3") (pinfunction "E_3") (pintype "passive"))
      (node (ref "R16") (pin "2") (pinfunction "2_2") (pintype "passive"))
    )
    (net (code "38") (name "Net-(T1-B)") (class "Default")
      (node (ref "R21") (pin "2") (pinfunction "2_2") (pintype "passive"))
      (node (ref "T1") (pin "3") (pinfunction "B_3") (pintype "passive"))
    )
    (net (code "39") (name "Net-(T1-C)") (class "Default")
      (node (ref "T1") (pin "2") (pinfunction "C_2") (pintype "passive"))
      (node (ref "TUBE2") (pin "1") (pinfunction "KL_1") (pintype "passive"))
    )
    (net (code "40") (name "Net-(T1-E)") (class "Default")
      (node (ref "R23") (pin "2") (pinfunction "2_2") (pintype "passive"))
      (node (ref "T1") (pin "1") (pinfunction "E_1") (pintype "passive"))
    )
    (net (code "41") (name "Net-(T2-B)") (class "Default")
      (node (ref "R18") (pin "2") (pinfunction "2_2") (pintype "passive"))
      (node (ref "T2") (pin "3") (pinfunction "B_3") (pintype "passive"))
    )
    (net (code "42") (name "Net-(T2-C)") (class "Default")
      (node (ref "T2") (pin "2") (pinfunction "C_2") (pintype "passive"))
      (node (ref "TUBE1") (pin "1") (pinfunction "KL_1") (pintype "passive"))
    )
    (net (code "43") (name "Net-(T2-E)") (class "Default")
      (node (ref "R20") (pin "2") (pinfunction "2_2") (pintype "passive"))
      (node (ref "T2") (pin "1") (pinfunction "E_1") (pintype "passive"))
    )
    (net (code "44") (name "Net-(U$7-D+)") (class "Default")
      (node (ref "U$7") (pin "5") (pinfunction "D+_5") (pintype "bidirectional"))
      (node (ref "X2") (pin "D+") (pinfunction "D+_D+") (pintype "bidirectional"))
    )
    (net (code "45") (name "Net-(U$7-D-)") (class "Default")
      (node (ref "U$7") (pin "6") (pinfunction "D-_6") (pintype "bidirectional"))
      (node (ref "X2") (pin "D-") (pinfunction "D-_D-") (pintype "bidirectional"))
    )
    (net (code "46") (name "Net-(U$7-XI)") (class "Default")
      (node (ref "C5") (pin "1") (pinfunction "1_1") (pintype "passive"))
      (node (ref "Q4") (pin "1") (pinfunction "1_1") (pintype "passive"))
      (node (ref "U$7") (pin "7") (pinfunction "XI_7") (pintype "bidirectional"))
    )
    (net (code "47") (name "Net-(U1-COMP)") (class "Default")
      (node (ref "C7") (pin "1") (pinfunction "1_1") (pintype "passive"))
      (node (ref "U1") (pin "3") (pinfunction "COMP_3") (pintype "input"))
    )
    (net (code "48") (name "Net-(U1-FA{slash}SYNC{slash}SD)") (class "Default")
      (node (ref "R12") (pin "2") (pinfunction "2_2") (pintype "passive"))
      (node (ref "U1") (pin "6") (pinfunction "FA/SYNC/SD_6") (pintype "input"))
    )
    (net (code "49") (name "Net-(U1-VCC)") (class "Default")
      (node (ref "C10") (pin "1") (pinfunction "1_1") (pintype "passive"))
      (node (ref "U1") (pin "9") (pinfunction "VCC_9") (pintype "power_in"))
    )
    (net (code "50") (name "Net-(U3-PROG)") (class "Default")
      (node (ref "R8") (pin "1") (pinfunction "1_1") (pintype "passive"))
      (node (ref "U3") (pin "5") (pinfunction "PROG_5") (pintype "input"))
    )
    (net (code "51") (name "Net-(U3-STAT)") (class "Default")
      (node (ref "R2") (pin "2") (pinfunction "2_2") (pintype "passive"))
      (node (ref "U3") (pin "1") (pinfunction "STAT_1") (pintype "output"))
    )
    (net (code "52") (name "Net-(U3-VBAT)") (class "Default")
      (node (ref "SJ1") (pin "1") (pinfunction "1_1") (pintype "passive"))
      (node (ref "U3") (pin "3") (pinfunction "VBAT_3") (pintype "power_in"))
    )
    (net (code "53") (name "Net-(U4-DRAIN)") (class "Default")
      (node (ref "U$6") (pin "PIN1") (pinfunction "PIN1_PIN1") (pintype "bidirectional"))
      (node (ref "U4") (pin "5") (pinfunction "DRAIN-1_5") (pintype "input"))
      (node (ref "U4") (pin "6") (pinfunction "DRAIN-2_6") (pintype "input"))
      (node (ref "U4") (pin "7") (pinfunction "DRAIN_7") (pintype "input"))
    )
    (net (code "54") (name "Net-(U5-CPOUT)") (class "Default")
      (node (ref "C21") (pin "1") (pinfunction "1_1") (pintype "passive"))
      (node (ref "U5") (pin "20") (pinfunction "CPOUT_20") (pintype "passive"))
    )
    (net (code "55") (name "Net-(U5-REGOUT)") (class "Default")
      (node (ref "C20") (pin "1") (pinfunction "1_1") (pintype "passive"))
      (node (ref "U5") (pin "10") (pinfunction "REGOUT_10") (pintype "passive"))
    )
    (net (code "56") (name "Net-(U5-VLOGIC)") (class "Default")
      (node (ref "C22") (pin "1") (pinfunction "1_1") (pintype "passive"))
      (node (ref "U5") (pin "8") (pinfunction "VLOGIC_8") (pintype "power_in"))
    )
    (net (code "57") (name "VBAT") (class "Default")
      (node (ref "C3") (pin "1") (pinfunction "1_1") (pintype "passive"))
      (node (ref "D4") (pin "A") (pinfunction "A_A") (pintype "passive"))
      (node (ref "SJ1") (pin "2") (pinfunction "2_2") (pintype "passive"))
      (node (ref "SV1") (pin "2") (pinfunction "2_2") (pintype "passive"))
      (node (ref "X1") (pin "2") (pinfunction "2_2") (pintype "passive"))
    )
    (net (code "58") (name "VBUS") (class "Default")
      (node (ref "C6") (pin "1") (pinfunction "1_1") (pintype "passive"))
      (node (ref "CHG") (pin "A") (pinfunction "A_A") (pintype "passive"))
      (node (ref "D4") (pin "C") (pinfunction "C_C") (pintype "passive"))
      (node (ref "R7") (pin "2") (pinfunction "2_2") (pintype "passive"))
      (node (ref "SV1") (pin "1") (pinfunction "1_1") (pintype "passive"))
      (node (ref "U2") (pin "1") (pinfunction "IN_1") (pintype "power_in"))
      (node (ref "U3") (pin "4") (pinfunction "VDD_4") (pintype "power_in"))
      (node (ref "X2") (pin "VBUS") (pinfunction "VBUS_VBUS") (pintype "power_in"))
      (node (ref "X3") (pin "1") (pinfunction "KL_1") (pintype "passive"))
    )
    (net (code "59") (name "unconnected-(IC2-PadCS0)") (class "Default")
      (node (ref "IC2") (pin "CS0") (pinfunction "CS0_CS0") (pintype "bidirectional"))
    )
    (net (code "60") (name "unconnected-(IC2-PadIO9)") (class "Default")
      (node (ref "IC2") (pin "IO9") (pinfunction "IO9_IO9") (pintype "bidirectional"))
    )
    (net (code "61") (name "unconnected-(IC2-PadIO10)") (class "Default")
      (node (ref "IC2") (pin "IO10") (pinfunction "IO10_IO10") (pintype "bidirectional"))
    )
    (net (code "62") (name "unconnected-(IC2-PadMISO)") (class "Default")
      (node (ref "IC2") (pin "MISO") (pinfunction "MISO_MISO") (pintype "bidirectional"))
    )
    (net (code "63") (name "unconnected-(IC2-PadMOSI)") (class "Default")
      (node (ref "IC2") (pin "MOSI") (pinfunction "MOSI_MOSI") (pintype "bidirectional"))
    )
    (net (code "64") (name "unconnected-(IC2-PadSCLK)") (class "Default")
      (node (ref "IC2") (pin "SCLK") (pinfunction "SCLK_SCLK") (pintype "bidirectional"))
    )
    (net (code "65") (name "unconnected-(U$7-CTS-Pad9)") (class "Default")
      (node (ref "U$7") (pin "9") (pinfunction "CTS_9") (pintype "bidirectional"))
    )
    (net (code "66") (name "unconnected-(U$7-DCD-Pad12)") (class "Default")
      (node (ref "U$7") (pin "12") (pinfunction "DCD_12") (pintype "bidirectional"))
    )
    (net (code "67") (name "unconnected-(U$7-DSR-Pad10)") (class "Default")
      (node (ref "U$7") (pin "10") (pinfunction "DSR_10") (pintype "bidirectional"))
    )
    (net (code "68") (name "unconnected-(U$7-RI-Pad11)") (class "Default")
      (node (ref "U$7") (pin "11") (pinfunction "RI_11") (pintype "bidirectional"))
    )
    (net (code "69") (name "unconnected-(U$7-RS232-Pad15)") (class "Default")
      (node (ref "U$7") (pin "15") (pinfunction "RS232_15") (pintype "bidirectional"))
    )
    (net (code "70") (name "unconnected-(U2-P4-Pad4)") (class "Default")
      (node (ref "U2") (pin "4") (pinfunction "P4_4") (pintype "bidirectional"))
    )
    (net (code "71") (name "unconnected-(U4-EMPTY-Pad8)") (class "Default")
      (node (ref "U4") (pin "8") (pinfunction "EMPTY_8") (pintype "bidirectional"))
    )
    (net (code "72") (name "unconnected-(U5-AD0-Pad9)") (class "Default")
      (node (ref "U5") (pin "9") (pinfunction "AD0_9") (pintype "input"))
    )
    (net (code "73") (name "unconnected-(U5-AUX_CL-Pad7)") (class "Default")
      (node (ref "U5") (pin "7") (pinfunction "AUX_CL_7") (pintype "input"))
    )
    (net (code "74") (name "unconnected-(U5-AUX_DA-Pad6)") (class "Default")
      (node (ref "U5") (pin "6") (pinfunction "AUX_DA_6") (pintype "bidirectional"))
    )
    (net (code "75") (name "unconnected-(U5-INT-Pad12)") (class "Default")
      (node (ref "U5") (pin "12") (pinfunction "INT_12") (pintype "output"))
    )
    (net (code "76") (name "unconnected-(U5-RESV-Pad19)") (class "Default")
      (node (ref "U5") (pin "19") (pinfunction "RESV_19") (pintype "passive"))
    )
    (net (code "77") (name "unconnected-(U5-RESV-Pad21)") (class "Default")
      (node (ref "U5") (pin "21") (pinfunction "RESV_21") (pintype "passive"))
    )
    (net (code "78") (name "unconnected-(U5-RESV-Pad22)") (class "Default")
      (node (ref "U5") (pin "22") (pinfunction "RESV_22") (pintype "passive"))
    )
    (net (code "79") (name "unconnected-(X2-PadID)") (class "Default")
      (node (ref "X2") (pin "ID") (pinfunction "ID_ID") (pintype "bidirectional"))
    )
  )
)
